# HB_SENSING.net
KiCad netlist of a schematic drawn in Altium Designer
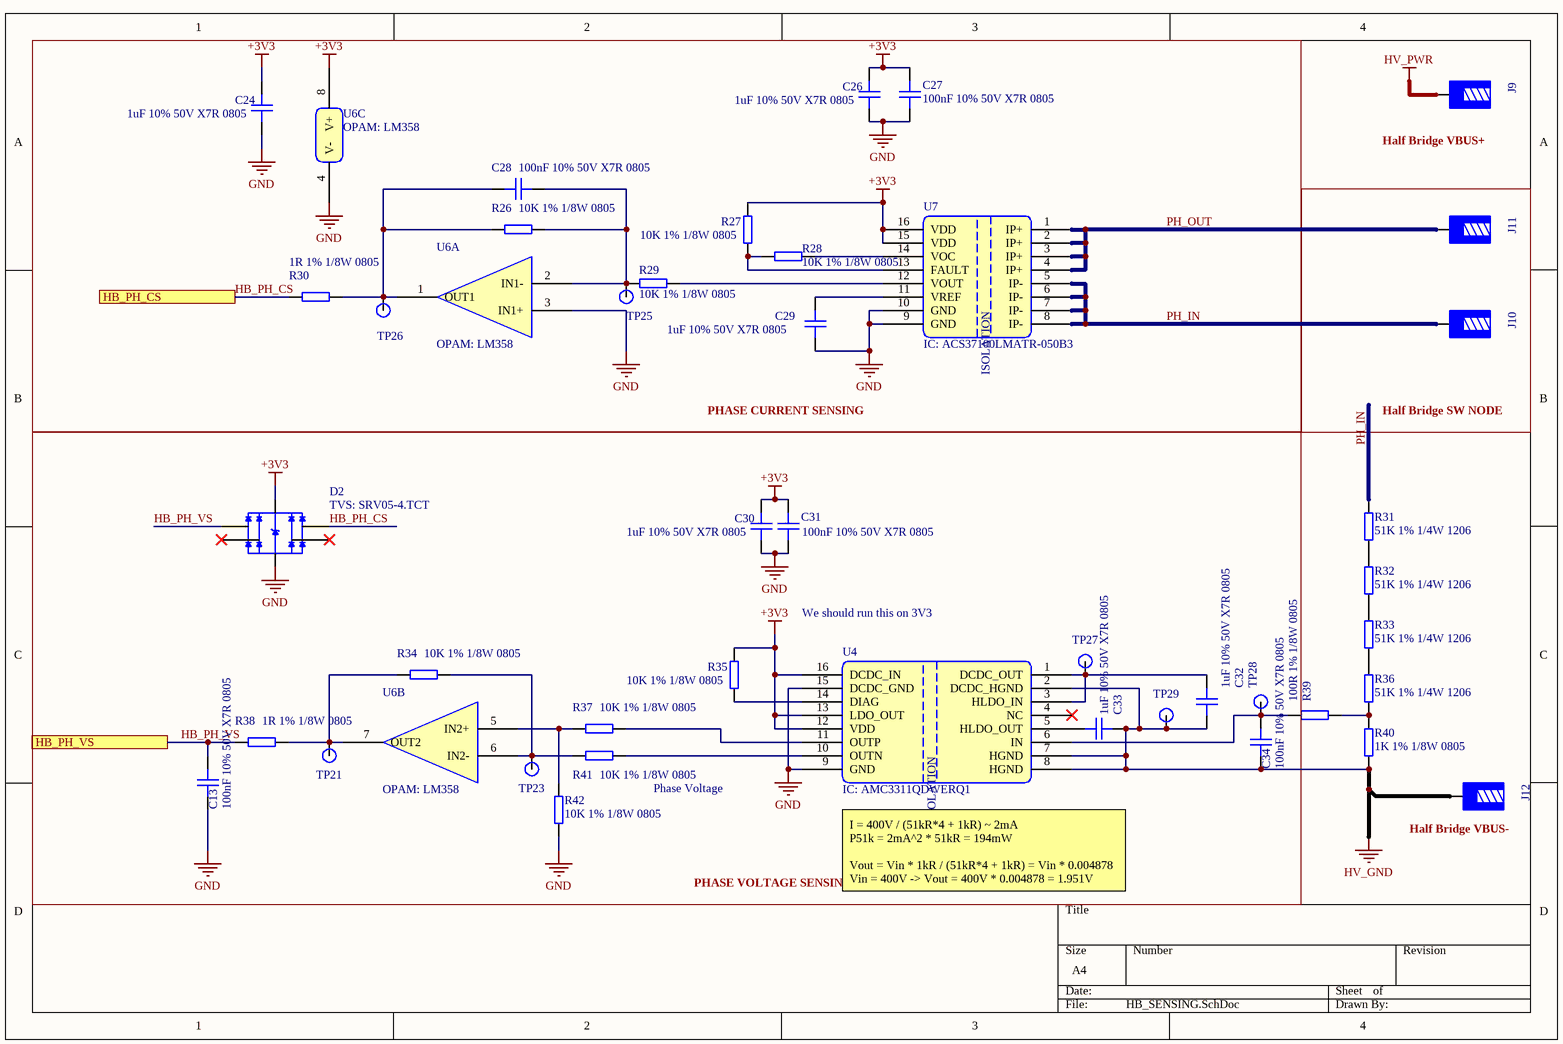
[diagram p0: HB_SENSING.SchDoc]

(export (version "E")
  (design (tool "Eeschema 10.0.6"))
  (components
    (comp (ref "C13")
      (value "100nF 10% 50V X7R 0805")
      (footprint "CAPC2012X10N")
      (description "Multilayer Ceramic Capacitors MLCC - SMD/SMT 50V 0.1uF X7R 0805 10%")
      (fields
        (field (name "MANUFACTURER") "Stackpole Electronics")
        (field (name "MANUFACTURER PART NUMBER") "CML0805X7R104KT50V")
      )
      (libsource (lib "EMEA- E-Tech Racing- I'Escola d'Enginyeria de Barcelona Est") (part "100nF 10% 50V X7R 0805-Symbol-1"))
    )
    (comp (ref "C24")
      (value "1uF 10% 50V X7R 0805")
      (footprint "CAPC2012X10N")
      (fields
        (field (name "MANUFACTURER PART NUMBER") "C2012X7R1H105K125AB")
        (field (name "MANUFACTURER") "TDK")
      )
      (libsource (lib "EMEA- E-Tech Racing- I'Escola d'Enginyeria de Barcelona Est") (part "68pF 10 630V C0G 0805"))
    )
    (comp (ref "C26")
      (value "1uF 10% 50V X7R 0805")
      (footprint "CAPC2012X10N")
      (fields
        (field (name "MANUFACTURER PART NUMBER") "C2012X7R1H105K125AB")
        (field (name "MANUFACTURER") "TDK")
      )
      (libsource (lib "EMEA- E-Tech Racing- I'Escola d'Enginyeria de Barcelona Est") (part "68pF 10 630V C0G 0805"))
    )
    (comp (ref "C27")
      (value "100nF 10% 50V X7R 0805")
      (footprint "CAPC2012X10N")
      (description "Multilayer Ceramic Capacitors MLCC - SMD/SMT 50V 0.1uF X7R 0805 10%")
      (fields
        (field (name "MANUFACTURER") "Stackpole Electronics")
        (field (name "MANUFACTURER PART NUMBER") "CML0805X7R104KT50V")
      )
      (libsource (lib "EMEA- E-Tech Racing- I'Escola d'Enginyeria de Barcelona Est") (part "100nF 10% 50V X7R 0805-Symbol-1"))
    )
    (comp (ref "C28")
      (value "100nF 10% 50V X7R 0805")
      (footprint "CAPC2012X10N")
      (description "Multilayer Ceramic Capacitors MLCC - SMD/SMT 50V 0.1uF X7R 0805 10%")
      (fields
        (field (name "MANUFACTURER") "Stackpole Electronics")
        (field (name "MANUFACTURER PART NUMBER") "CML0805X7R104KT50V")
      )
      (libsource (lib "EMEA- E-Tech Racing- I'Escola d'Enginyeria de Barcelona Est") (part "100nF 10% 50V X7R 0805-Symbol-1"))
    )
    (comp (ref "C29")
      (value "1uF 10% 50V X7R 0805")
      (footprint "CAPC2012X10N")
      (fields
        (field (name "MANUFACTURER PART NUMBER") "C2012X7R1H105K125AB")
        (field (name "MANUFACTURER") "TDK")
      )
      (libsource (lib "EMEA- E-Tech Racing- I'Escola d'Enginyeria de Barcelona Est") (part "68pF 10 630V C0G 0805"))
    )
    (comp (ref "C30")
      (value "1uF 10% 50V X7R 0805")
      (footprint "CAPC2012X10N")
      (fields
        (field (name "MANUFACTURER PART NUMBER") "C2012X7R1H105K125AB")
        (field (name "MANUFACTURER") "TDK")
      )
      (libsource (lib "EMEA- E-Tech Racing- I'Escola d'Enginyeria de Barcelona Est") (part "68pF 10 630V C0G 0805"))
    )
    (comp (ref "C31")
      (value "100nF 10% 50V X7R 0805")
      (footprint "CAPC2012X10N")
      (description "Multilayer Ceramic Capacitors MLCC - SMD/SMT 50V 0.1uF X7R 0805 10%")
      (fields
        (field (name "MANUFACTURER") "Stackpole Electronics")
        (field (name "MANUFACTURER PART NUMBER") "CML0805X7R104KT50V")
      )
      (libsource (lib "EMEA- E-Tech Racing- I'Escola d'Enginyeria de Barcelona Est") (part "100nF 10% 50V X7R 0805-Symbol-1"))
    )
    (comp (ref "C32")
      (value "1uF 10% 50V X7R 0805")
      (footprint "CAPC2012X10N")
      (fields
        (field (name "MANUFACTURER PART NUMBER") "C2012X7R1H105K125AB")
        (field (name "MANUFACTURER") "TDK")
      )
      (libsource (lib "EMEA- E-Tech Racing- I'Escola d'Enginyeria de Barcelona Est") (part "68pF 10 630V C0G 0805"))
    )
    (comp (ref "C33")
      (value "1uF 10% 50V X7R 0805")
      (footprint "CAPC2012X10N")
      (fields
        (field (name "MANUFACTURER PART NUMBER") "C2012X7R1H105K125AB")
        (field (name "MANUFACTURER") "TDK")
      )
      (libsource (lib "EMEA- E-Tech Racing- I'Escola d'Enginyeria de Barcelona Est") (part "68pF 10 630V C0G 0805"))
    )
    (comp (ref "C34")
      (value "100nF 10% 50V X7R 0805")
      (footprint "CAPC2012X10N")
      (description "Multilayer Ceramic Capacitors MLCC - SMD/SMT 50V 0.1uF X7R 0805 10%")
      (fields
        (field (name "MANUFACTURER") "Stackpole Electronics")
        (field (name "MANUFACTURER PART NUMBER") "CML0805X7R104KT50V")
      )
      (libsource (lib "EMEA- E-Tech Racing- I'Escola d'Enginyeria de Barcelona Est") (part "100nF 10% 50V X7R 0805-Symbol-1"))
    )
    (comp (ref "D2")
      (value "TVS: SRV05-4.TCT")
      (footprint "SMTC-SOT23-6_V")
      (description "SRV Series 17.5 V 3 pF SMT RailClamp® Low Capacitance TVS Diode Array SOT-23-6")
      (fields (field (name "VOLTAGE") "5V") (field (name "MANUFACTURER") "Semtech"))
      (libsource (lib "EMEA- E-Tech Racing- I'Escola d'Enginyeria de Barcelona Est") (part "SRV05-4.TCT"))
    )
    (comp (ref "J9")
      (value "CON1: M5 PCB Terminal")
      (footprint "CON1: M5 PCB Terminal-Footprint-1")
      (fields (field (name "MANUFACTURER") "Lab") (field (name "MANUFACTURER PART NUMBER") "M5 PCB Terminal"))
      (libsource (lib "EMEA- E-Tech Racing- I'Escola d'Enginyeria de Barcelona Est") (part "CON1{colon} M5 PCB Terminal-Symbol-1"))
    )
    (comp (ref "J10")
      (value "CON1: M5 PCB Terminal")
      (footprint "CON1: M5 PCB Terminal-Footprint-1")
      (fields (field (name "MANUFACTURER") "Lab") (field (name "MANUFACTURER PART NUMBER") "M5 PCB Terminal"))
      (libsource (lib "EMEA- E-Tech Racing- I'Escola d'Enginyeria de Barcelona Est") (part "CON1{colon} M5 PCB Terminal-Symbol-1"))
    )
    (comp (ref "J11")
      (value "CON1: M5 PCB Terminal")
      (footprint "CON1: M5 PCB Terminal-Footprint-1")
      (fields (field (name "MANUFACTURER") "Lab") (field (name "MANUFACTURER PART NUMBER") "M5 PCB Terminal"))
      (libsource (lib "EMEA- E-Tech Racing- I'Escola d'Enginyeria de Barcelona Est") (part "CON1{colon} M5 PCB Terminal-Symbol-1"))
    )
    (comp (ref "J12")
      (value "CON1: M5 PCB Terminal")
      (footprint "CON1: M5 PCB Terminal-Footprint-1")
      (fields (field (name "MANUFACTURER") "Lab") (field (name "MANUFACTURER PART NUMBER") "M5 PCB Terminal"))
      (libsource (lib "EMEA- E-Tech Racing- I'Escola d'Enginyeria de Barcelona Est") (part "CON1{colon} M5 PCB Terminal-Symbol-1"))
    )
    (comp (ref "R26")
      (value "10K 1% 1/8W 0805")
      (footprint "RESC2012X05N")
      (description "Res Thick Film 0805 10K Ohm 1% 0.125W ±100ppm/°C Molded SMD Paper T/R")
      (fields
        (field (name "MANUFACTURER") "Stackpole Electronics")
        (field (name "MANUFACTURER PART NUMBER") "RMCF0805FT10K0")
      )
      (libsource (lib "EMEA- E-Tech Racing- I'Escola d'Enginyeria de Barcelona Est") (part "100R 1 1/8W 0805"))
    )
    (comp (ref "R27")
      (value "10K 1% 1/8W 0805")
      (footprint "RESC2012X05N")
      (description "Res Thick Film 0805 10K Ohm 1% 0.125W ±100ppm/°C Molded SMD Paper T/R")
      (fields
        (field (name "MANUFACTURER") "Stackpole Electronics")
        (field (name "MANUFACTURER PART NUMBER") "RMCF0805FT10K0")
      )
      (libsource (lib "EMEA- E-Tech Racing- I'Escola d'Enginyeria de Barcelona Est") (part "100R 1 1/8W 0805"))
    )
    (comp (ref "R28")
      (value "10K 1% 1/8W 0805")
      (footprint "RESC2012X05N")
      (description "Res Thick Film 0805 10K Ohm 1% 0.125W ±100ppm/°C Molded SMD Paper T/R")
      (fields
        (field (name "MANUFACTURER") "Stackpole Electronics")
        (field (name "MANUFACTURER PART NUMBER") "RMCF0805FT10K0")
      )
      (libsource (lib "EMEA- E-Tech Racing- I'Escola d'Enginyeria de Barcelona Est") (part "100R 1 1/8W 0805"))
    )
    (comp (ref "R29")
      (value "10K 1% 1/8W 0805")
      (footprint "RESC2012X05N")
      (description "Res Thick Film 0805 10K Ohm 1% 0.125W ±100ppm/°C Molded SMD Paper T/R")
      (fields
        (field (name "MANUFACTURER") "Stackpole Electronics")
        (field (name "MANUFACTURER PART NUMBER") "RMCF0805FT10K0")
      )
      (libsource (lib "EMEA- E-Tech Racing- I'Escola d'Enginyeria de Barcelona Est") (part "100R 1 1/8W 0805"))
    )
    (comp (ref "R30")
      (value "1R 1% 1/8W 0805")
      (footprint "RESC2012X05N")
      (description "Res Thick Film 0805 1 Ohm 1% 0.125W ±100ppm/°C Molded SMD Paper T/R")
      (fields
        (field (name "MANUFACTURER PART NUMBER") "RMCF0805FT1R00")
        (field (name "MANUFACTURER") "Stackpole Electronics")
      )
      (libsource (lib "EMEA- E-Tech Racing- I'Escola d'Enginyeria de Barcelona Est") (part "100R 1 1/8W 0805"))
    )
    (comp (ref "R31")
      (value "51K 1% 1/4W 1206")
      (footprint "RESC3116X06N")
      (description "Res Thick Film 1206 51K Ohm 1% 0.25W(1/4W) ±100ppm/C Pad SMD T/R Automotive AEC-Q200")
      (fields (field (name "MANUFACTURER") "Stackpole Electronics") (field (name "TOLERANCE") "5%"))
      (libsource (lib "EMEA- E-Tech Racing- I'Escola d'Enginyeria de Barcelona Est") (part "100R 1 1/8W 0805"))
    )
    (comp (ref "R32")
      (value "51K 1% 1/4W 1206")
      (footprint "RESC3116X06N")
      (description "Res Thick Film 1206 51K Ohm 1% 0.25W(1/4W) ±100ppm/C Pad SMD T/R Automotive AEC-Q200")
      (fields (field (name "MANUFACTURER") "Stackpole Electronics") (field (name "TOLERANCE") "5%"))
      (libsource (lib "EMEA- E-Tech Racing- I'Escola d'Enginyeria de Barcelona Est") (part "100R 1 1/8W 0805"))
    )
    (comp (ref "R33")
      (value "51K 1% 1/4W 1206")
      (footprint "RESC3116X06N")
      (description "Res Thick Film 1206 51K Ohm 1% 0.25W(1/4W) ±100ppm/C Pad SMD T/R Automotive AEC-Q200")
      (fields (field (name "MANUFACTURER") "Stackpole Electronics") (field (name "TOLERANCE") "5%"))
      (libsource (lib "EMEA- E-Tech Racing- I'Escola d'Enginyeria de Barcelona Est") (part "100R 1 1/8W 0805"))
    )
    (comp (ref "R34")
      (value "10K 1% 1/8W 0805")
      (footprint "RESC2012X05N")
      (description "Res Thick Film 0805 10K Ohm 1% 0.125W ±100ppm/°C Molded SMD Paper T/R")
      (fields
        (field (name "MANUFACTURER") "Stackpole Electronics")
        (field (name "MANUFACTURER PART NUMBER") "RMCF0805FT10K0")
      )
      (libsource (lib "EMEA- E-Tech Racing- I'Escola d'Enginyeria de Barcelona Est") (part "100R 1 1/8W 0805"))
    )
    (comp (ref "R35")
      (value "10K 1% 1/8W 0805")
      (footprint "RESC2012X05N")
      (description "Res Thick Film 0805 10K Ohm 1% 0.125W ±100ppm/°C Molded SMD Paper T/R")
      (fields
        (field (name "MANUFACTURER") "Stackpole Electronics")
        (field (name "MANUFACTURER PART NUMBER") "RMCF0805FT10K0")
      )
      (libsource (lib "EMEA- E-Tech Racing- I'Escola d'Enginyeria de Barcelona Est") (part "100R 1 1/8W 0805"))
    )
    (comp (ref "R36")
      (value "51K 1% 1/4W 1206")
      (footprint "RESC3116X06N")
      (description "Res Thick Film 1206 51K Ohm 1% 0.25W(1/4W) ±100ppm/C Pad SMD T/R Automotive AEC-Q200")
      (fields (field (name "MANUFACTURER") "Stackpole Electronics") (field (name "TOLERANCE") "5%"))
      (libsource (lib "EMEA- E-Tech Racing- I'Escola d'Enginyeria de Barcelona Est") (part "100R 1 1/8W 0805"))
    )
    (comp (ref "R37")
      (value "10K 1% 1/8W 0805")
      (footprint "RESC2012X05N")
      (description "Res Thick Film 0805 10K Ohm 1% 0.125W ±100ppm/°C Molded SMD Paper T/R")
      (fields
        (field (name "MANUFACTURER") "Stackpole Electronics")
        (field (name "MANUFACTURER PART NUMBER") "RMCF0805FT10K0")
      )
      (libsource (lib "EMEA- E-Tech Racing- I'Escola d'Enginyeria de Barcelona Est") (part "100R 1 1/8W 0805"))
    )
    (comp (ref "R38")
      (value "1R 1% 1/8W 0805")
      (footprint "RESC2012X05N")
      (description "Res Thick Film 0805 1 Ohm 1% 0.125W ±100ppm/°C Molded SMD Paper T/R")
      (fields
        (field (name "MANUFACTURER PART NUMBER") "RMCF0805FT1R00")
        (field (name "MANUFACTURER") "Stackpole Electronics")
      )
      (libsource (lib "EMEA- E-Tech Racing- I'Escola d'Enginyeria de Barcelona Est") (part "100R 1 1/8W 0805"))
    )
    (comp (ref "R39")
      (value "100R 1% 1/8W 0805")
      (footprint "RESC2012X05N")
      (description "Res Thick Film 0805 100 Ohm 1% 0.125W ±100ppm/°C Molded SMD Paper T/R")
      (fields (field (name "TOLERANCE") "1%") (field (name "MANUFACTURER PART NUMBER") "RMCF0805FT100R"))
      (libsource (lib "EMEA- E-Tech Racing- I'Escola d'Enginyeria de Barcelona Est") (part "100R 1 1/8W 0805"))
    )
    (comp (ref "R40")
      (value "1K 1% 1/8W 0805")
      (footprint "RESC2012X05N")
      (description "Res Thick Film 0805 1K Ohm 1% 0.125W ±100ppm/°C Molded SMD Paper T/R")
      (fields (field (name "TOLERANCE") "1%") (field (name "MANUFACTURER") "Stackpole Electronics"))
      (libsource (lib "EMEA- E-Tech Racing- I'Escola d'Enginyeria de Barcelona Est") (part "100R 1 1/8W 0805"))
    )
    (comp (ref "R41")
      (value "10K 1% 1/8W 0805")
      (footprint "RESC2012X05N")
      (description "Res Thick Film 0805 10K Ohm 1% 0.125W ±100ppm/°C Molded SMD Paper T/R")
      (fields
        (field (name "MANUFACTURER") "Stackpole Electronics")
        (field (name "MANUFACTURER PART NUMBER") "RMCF0805FT10K0")
      )
      (libsource (lib "EMEA- E-Tech Racing- I'Escola d'Enginyeria de Barcelona Est") (part "100R 1 1/8W 0805"))
    )
    (comp (ref "R42")
      (value "10K 1% 1/8W 0805")
      (footprint "RESC2012X05N")
      (description "Res Thick Film 0805 10K Ohm 1% 0.125W ±100ppm/°C Molded SMD Paper T/R")
      (fields
        (field (name "MANUFACTURER") "Stackpole Electronics")
        (field (name "MANUFACTURER PART NUMBER") "RMCF0805FT10K0")
      )
      (libsource (lib "EMEA- E-Tech Racing- I'Escola d'Enginyeria de Barcelona Est") (part "100R 1 1/8W 0805"))
    )
    (comp (ref "TP21")
      (value "TestPoint")
      (footprint "Test Point-Footprint-1")
      (libsource (lib "EMEA- E-Tech Racing- I'Escola d'Enginyeria de Barcelona Est") (part "New symbol 1"))
    )
    (comp (ref "TP23")
      (value "TestPoint")
      (footprint "Test Point-Footprint-1")
      (libsource (lib "EMEA- E-Tech Racing- I'Escola d'Enginyeria de Barcelona Est") (part "New symbol 1"))
    )
    (comp (ref "TP25")
      (value "TestPoint")
      (footprint "Test Point-Footprint-1")
      (libsource (lib "EMEA- E-Tech Racing- I'Escola d'Enginyeria de Barcelona Est") (part "New symbol 1"))
    )
    (comp (ref "TP26")
      (value "TestPoint")
      (footprint "Test Point-Footprint-1")
      (libsource (lib "EMEA- E-Tech Racing- I'Escola d'Enginyeria de Barcelona Est") (part "New symbol 1"))
    )
    (comp (ref "TP27")
      (value "TestPoint")
      (footprint "Test Point-Footprint-1")
      (libsource (lib "EMEA- E-Tech Racing- I'Escola d'Enginyeria de Barcelona Est") (part "New symbol 1"))
    )
    (comp (ref "TP28")
      (value "TestPoint")
      (footprint "Test Point-Footprint-1")
      (libsource (lib "EMEA- E-Tech Racing- I'Escola d'Enginyeria de Barcelona Est") (part "New symbol 1"))
    )
    (comp (ref "TP29")
      (value "TestPoint")
      (footprint "Test Point-Footprint-1")
      (libsource (lib "EMEA- E-Tech Racing- I'Escola d'Enginyeria de Barcelona Est") (part "New symbol 1"))
    )
    (comp (ref "U4")
      (value "IC: AMC3311QDWERQ1")
      (footprint "SOIC127P1030X265-16N")
      (fields
        (field (name "MANUFACTURER") "Texas Instruments")
        (field (name "MANUFACTURER PART NUMBER") "AMC3311QDWERQ1")
      )
      (libsource (lib "EMEA- E-Tech Racing- I'Escola d'Enginyeria de Barcelona Est") (part "AMC3311"))
    )
    (comp (ref "U6")
      (value "OPAM: LM358")
      (footprint "FP-D0008A-IPC_C")
      (description "Dual, 30-V, 700-kHz, 3-mV offset voltage operational amplifier 8-SOIC 0 to 70")
      (fields
        (field (name "MANUFACTURER") "Texas Instruments")
        (field (name "MANUFACTURER PART NUMBER") "LM358BAIDR")
      )
      (libsource (lib "EMEA- E-Tech Racing- I'Escola d'Enginyeria de Barcelona Est") (part "OP{colon} LM358"))
    )
    (comp (ref "U7")
      (value "IC: ACS37100LMATR-050B3")
      (footprint "SOIC127P1030X265-16N")
      (description "Magnetoresistive Sensor")
      (fields
        (field (name "MANUFACTURER PART NUMBER") "ACS37100LMATR-050B3")
        (field (name "MANUFACTURER") "Allegro MicroSystems")
      )
      (libsource (lib "EMEA- E-Tech Racing- I'Escola d'Enginyeria de Barcelona Est") (part "ACS37100LMATR-050B3-Symbol-1"))
    )
  )
  (nets
    (net (code "1") (name "+3V3") (class "Default")
      (node (ref "C24") (pin "2") (pinfunction "2_2") (pintype "passive"))
      (node (ref "C26") (pin "2") (pinfunction "2_2") (pintype "passive"))
      (node (ref "C27") (pin "2") (pinfunction "2_2") (pintype "passive"))
      (node (ref "C30") (pin "2") (pinfunction "2_2") (pintype "passive"))
      (node (ref "C31") (pin "2") (pinfunction "2_2") (pintype "passive"))
      (node (ref "D2") (pin "5") (pinfunction "5_5") (pintype "passive"))
      (node (ref "R27") (pin "1") (pinfunction "1_1") (pintype "passive"))
      (node (ref "R35") (pin "1") (pinfunction "1_1") (pintype "passive"))
      (node (ref "U4") (pin "12") (pinfunction "VDD_12") (pintype "passive"))
      (node (ref "U4") (pin "13") (pinfunction "LDO_OUT_13") (pintype "passive"))
      (node (ref "U4") (pin "16") (pinfunction "DCDC_IN_16") (pintype "passive"))
      (node (ref "U6") (pin "8") (pinfunction "V+_8") (pintype "passive"))
      (node (ref "U7") (pin "15") (pinfunction "VDD_15") (pintype "passive"))
      (node (ref "U7") (pin "16") (pinfunction "VDD_16") (pintype "passive"))
    )
    (net (code "2") (name "/HB_PH_CS") (class "Default")
      (node (ref "D2") (pin "4") (pinfunction "4_4") (pintype "passive"))
      (node (ref "R30") (pin "1") (pinfunction "1_1") (pintype "passive"))
    )
    (net (code "3") (name "/HB_PH_VS") (class "Default")
      (node (ref "C13") (pin "2") (pinfunction "2_2") (pintype "passive"))
      (node (ref "D2") (pin "1") (pinfunction "1_1") (pintype "passive"))
      (node (ref "R38") (pin "1") (pinfunction "1_1") (pintype "passive"))
    )
    (net (code "4") (name "/PH_IN") (class "Default")
      (node (ref "J10") (pin "1") (pinfunction "1_1") (pintype "passive"))
      (node (ref "R31") (pin "2") (pinfunction "2_2") (pintype "passive"))
      (node (ref "U7") (pin "5") (pinfunction "IP-_5") (pintype "passive"))
      (node (ref "U7") (pin "6") (pinfunction "IP-_6") (pintype "passive"))
      (node (ref "U7") (pin "7") (pinfunction "IP-_7") (pintype "passive"))
      (node (ref "U7") (pin "8") (pinfunction "IP-_8") (pintype "passive"))
    )
    (net (code "5") (name "/PH_OUT") (class "Default")
      (node (ref "J11") (pin "1") (pinfunction "1_1") (pintype "passive"))
      (node (ref "U7") (pin "1") (pinfunction "IP+_1") (pintype "passive"))
      (node (ref "U7") (pin "2") (pinfunction "IP+_2") (pintype "passive"))
      (node (ref "U7") (pin "3") (pinfunction "IP+_3") (pintype "passive"))
      (node (ref "U7") (pin "4") (pinfunction "IP+_4") (pintype "passive"))
    )
    (net (code "6") (name "GND") (class "Default")
      (node (ref "C13") (pin "1") (pinfunction "1_1") (pintype "passive"))
      (node (ref "C24") (pin "1") (pinfunction "1_1") (pintype "passive"))
      (node (ref "C26") (pin "1") (pinfunction "1_1") (pintype "passive"))
      (node (ref "C27") (pin "1") (pinfunction "1_1") (pintype "passive"))
      (node (ref "C29") (pin "1") (pinfunction "1_1") (pintype "passive"))
      (node (ref "C30") (pin "1") (pinfunction "1_1") (pintype "passive"))
      (node (ref "C31") (pin "1") (pinfunction "1_1") (pintype "passive"))
      (node (ref "D2") (pin "2") (pinfunction "2_2") (pintype "passive"))
      (node (ref "R42") (pin "1") (pinfunction "1_1") (pintype "passive"))
      (node (ref "U4") (pin "15") (pinfunction "DCDC_GND_15") (pintype "passive"))
      (node (ref "U4") (pin "9") (pinfunction "GND_9") (pintype "passive"))
      (node (ref "U6") (pin "3") (pinfunction "IN1+_3") (pintype "passive"))
      (node (ref "U6") (pin "4") (pinfunction "V-_4") (pintype "passive"))
      (node (ref "U7") (pin "10") (pinfunction "GND_10") (pintype "passive"))
      (node (ref "U7") (pin "9") (pinfunction "GND_9") (pintype "passive"))
    )
    (net (code "7") (name "HV_GND") (class "Default")
      (node (ref "C32") (pin "1") (pinfunction "1_1") (pintype "passive"))
      (node (ref "C33") (pin "1") (pinfunction "1_1") (pintype "passive"))
      (node (ref "C34") (pin "1") (pinfunction "1_1") (pintype "passive"))
      (node (ref "J12") (pin "1") (pinfunction "1_1") (pintype "passive"))
      (node (ref "R40") (pin "1") (pinfunction "1_1") (pintype "passive"))
      (node (ref "TP29") (pin "1") (pinfunction "1_1") (pintype "passive"))
      (node (ref "U4") (pin "2") (pinfunction "DCDC_HGND_2") (pintype "passive"))
      (node (ref "U4") (pin "7") (pinfunction "HGND_7") (pintype "passive"))
      (node (ref "U4") (pin "8") (pinfunction "HGND_8") (pintype "passive"))
    )
    (net (code "8") (name "HV_PWR") (class "Default")
      (node (ref "J9") (pin "1") (pinfunction "1_1") (pintype "passive"))
    )
    (net (code "9") (name "Net-(R31-Pad1)") (class "Default")
      (node (ref "R31") (pin "1") (pinfunction "1_1") (pintype "passive"))
      (node (ref "R32") (pin "2") (pinfunction "2_2") (pintype "passive"))
    )
    (net (code "10") (name "Net-(R32-Pad1)") (class "Default")
      (node (ref "R32") (pin "1") (pinfunction "1_1") (pintype "passive"))
      (node (ref "R33") (pin "2") (pinfunction "2_2") (pintype "passive"))
    )
    (net (code "11") (name "Net-(R33-Pad1)") (class "Default")
      (node (ref "R33") (pin "1") (pinfunction "1_1") (pintype "passive"))
      (node (ref "R36") (pin "2") (pinfunction "2_2") (pintype "passive"))
    )
    (net (code "12") (name "Net-(R36-Pad1)") (class "Default")
      (node (ref "R36") (pin "1") (pinfunction "1_1") (pintype "passive"))
      (node (ref "R39") (pin "1") (pinfunction "1_1") (pintype "passive"))
      (node (ref "R40") (pin "2") (pinfunction "2_2") (pintype "passive"))
    )
    (net (code "13") (name "Net-(U4-DCDC_OUT)") (class "Default")
      (node (ref "C32") (pin "2") (pinfunction "2_2") (pintype "passive"))
      (node (ref "TP27") (pin "1") (pinfunction "1_1") (pintype "passive"))
      (node (ref "U4") (pin "1") (pinfunction "DCDC_OUT_1") (pintype "passive"))
      (node (ref "U4") (pin "3") (pinfunction "HLDO_IN_3") (pintype "passive"))
    )
    (net (code "14") (name "Net-(U4-DIAG)") (class "Default")
      (node (ref "R35") (pin "2") (pinfunction "2_2") (pintype "passive"))
      (node (ref "U4") (pin "14") (pinfunction "DIAG_14") (pintype "passive"))
    )
    (net (code "15") (name "Net-(U4-HLDO_OUT)") (class "Default")
      (node (ref "C33") (pin "2") (pinfunction "2_2") (pintype "passive"))
      (node (ref "U4") (pin "5") (pinfunction "HLDO_OUT_5") (pintype "passive"))
    )
    (net (code "16") (name "Net-(U4-IN)") (class "Default")
      (node (ref "C34") (pin "2") (pinfunction "2_2") (pintype "passive"))
      (node (ref "R39") (pin "2") (pinfunction "2_2") (pintype "passive"))
      (node (ref "TP28") (pin "1") (pinfunction "1_1") (pintype "passive"))
      (node (ref "U4") (pin "6") (pinfunction "IN_6") (pintype "passive"))
    )
    (net (code "17") (name "Net-(U4-OUTN)") (class "Default")
      (node (ref "R41") (pin "2") (pinfunction "2_2") (pintype "passive"))
      (node (ref "U4") (pin "10") (pinfunction "OUTN_10") (pintype "passive"))
    )
    (net (code "18") (name "Net-(U4-OUTP)") (class "Default")
      (node (ref "R37") (pin "2") (pinfunction "2_2") (pintype "passive"))
      (node (ref "U4") (pin "11") (pinfunction "OUTP_11") (pintype "passive"))
    )
    (net (code "19") (name "Net-(U6A-IN1-)") (class "Default")
      (node (ref "C28") (pin "2") (pinfunction "2_2") (pintype "passive"))
      (node (ref "R26") (pin "2") (pinfunction "2_2") (pintype "passive"))
      (node (ref "R29") (pin "1") (pinfunction "1_1") (pintype "passive"))
      (node (ref "TP25") (pin "1") (pinfunction "1_1") (pintype "passive"))
      (node (ref "U6") (pin "2") (pinfunction "IN1-_2") (pintype "passive"))
    )
    (net (code "20") (name "Net-(U6A-OUT1)") (class "Default")
      (node (ref "C28") (pin "1") (pinfunction "1_1") (pintype "passive"))
      (node (ref "R26") (pin "1") (pinfunction "1_1") (pintype "passive"))
      (node (ref "R30") (pin "2") (pinfunction "2_2") (pintype "passive"))
      (node (ref "TP26") (pin "1") (pinfunction "1_1") (pintype "passive"))
      (node (ref "U6") (pin "1") (pinfunction "OUT1_1") (pintype "passive"))
    )
    (net (code "21") (name "Net-(U6B-IN2+)") (class "Default")
      (node (ref "R37") (pin "1") (pinfunction "1_1") (pintype "passive"))
      (node (ref "R42") (pin "2") (pinfunction "2_2") (pintype "passive"))
      (node (ref "U6") (pin "5") (pinfunction "IN2+_5") (pintype "passive"))
    )
    (net (code "22") (name "Net-(U6B-IN2-)") (class "Default")
      (node (ref "R34") (pin "2") (pinfunction "2_2") (pintype "passive"))
      (node (ref "R41") (pin "1") (pinfunction "1_1") (pintype "passive"))
      (node (ref "TP23") (pin "1") (pinfunction "1_1") (pintype "passive"))
      (node (ref "U6") (pin "6") (pinfunction "IN2-_6") (pintype "passive"))
    )
    (net (code "23") (name "Net-(U6B-OUT2)") (class "Default")
      (node (ref "R34") (pin "1") (pinfunction "1_1") (pintype "passive"))
      (node (ref "R38") (pin "2") (pinfunction "2_2") (pintype "passive"))
      (node (ref "TP21") (pin "1") (pinfunction "1_1") (pintype "passive"))
      (node (ref "U6") (pin "7") (pinfunction "OUT2_7") (pintype "passive"))
    )
    (net (code "24") (name "Net-(U7-FAULT)") (class "Default")
      (node (ref "R27") (pin "2") (pinfunction "2_2") (pintype "passive"))
      (node (ref "R28") (pin "1") (pinfunction "1_1") (pintype "passive"))
      (node (ref "U7") (pin "13") (pinfunction "FAULT_13") (pintype "passive"))
    )
    (net (code "25") (name "Net-(U7-VOC)") (class "Default")
      (node (ref "R28") (pin "2") (pinfunction "2_2") (pintype "passive"))
      (node (ref "U7") (pin "14") (pinfunction "VOC_14") (pintype "passive"))
    )
    (net (code "26") (name "Net-(U7-VOUT)") (class "Default")
      (node (ref "R29") (pin "2") (pinfunction "2_2") (pintype "passive"))
      (node (ref "U7") (pin "12") (pinfunction "VOUT_12") (pintype "passive"))
    )
    (net (code "27") (name "Net-(U7-VREF)") (class "Default")
      (node (ref "C29") (pin "2") (pinfunction "2_2") (pintype "passive"))
      (node (ref "U7") (pin "11") (pinfunction "VREF_11") (pintype "passive"))
    )
    (net (code "28") (name "unconnected-(D2-Pad3)") (class "Default")
      (node (ref "D2") (pin "3") (pinfunction "3_3") (pintype "passive+no_connect"))
    )
    (net (code "29") (name "unconnected-(D2-Pad6)") (class "Default")
      (node (ref "D2") (pin "6") (pinfunction "6_6") (pintype "passive+no_connect"))
    )
    (net (code "30") (name "unconnected-(U4-NC-Pad4)") (class "Default")
      (node (ref "U4") (pin "4") (pinfunction "NC_4") (pintype "passive+no_connect"))
    )
  )
)
